# 1DD-17-mk-1_2.net
KiCad netlist of a schematic drawn in EAGLE
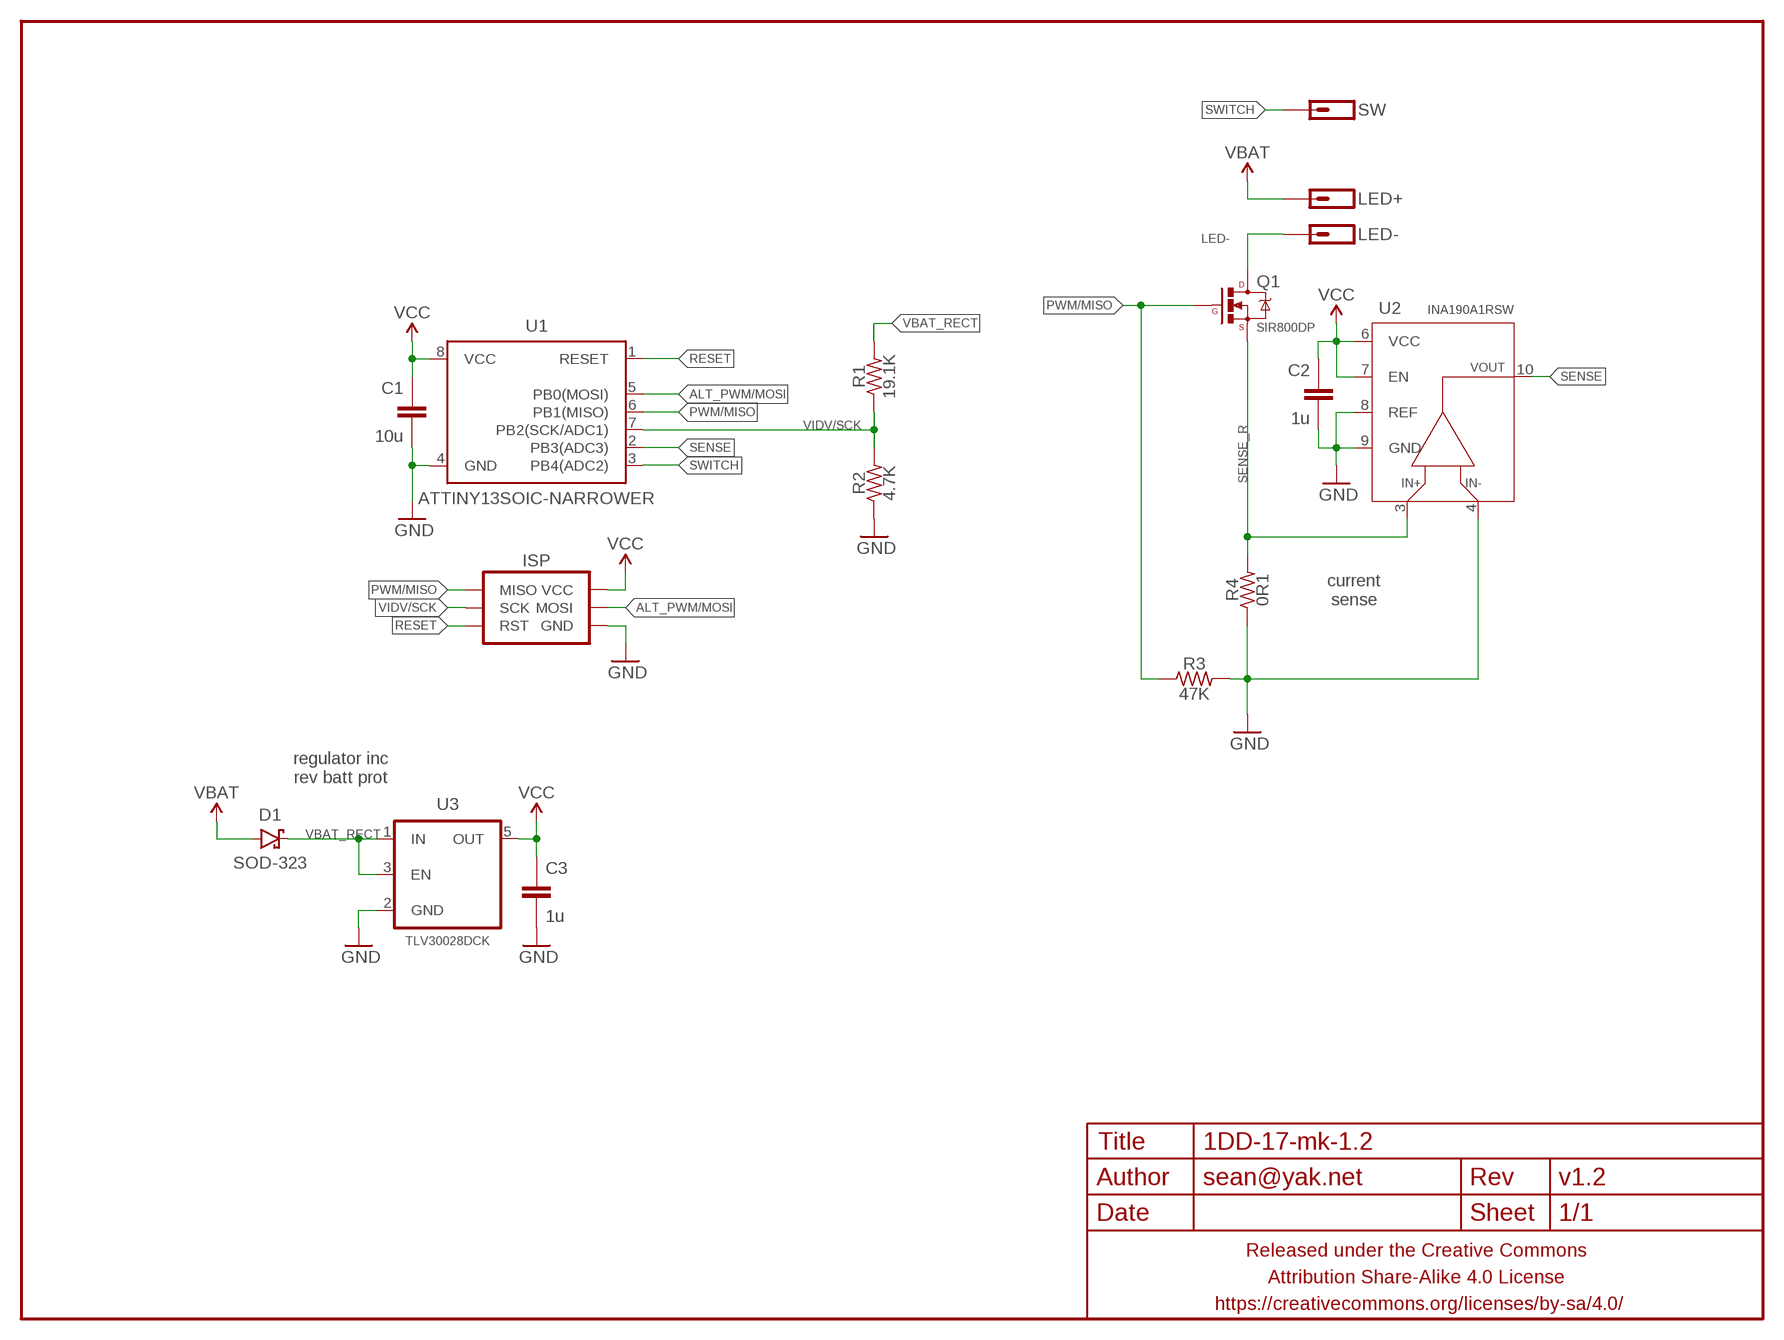
[diagram p0: schematic, sheet 1]

(export (version "E")
  (design (tool "Eeschema 10.0.6"))
  (components
    (comp (ref "C1")
      (value "10u")
      (footprint "eagle-import:C0402")
      (libsource (lib "eagle-import") (part "CAPACITOR-CERAMICC0402"))
    )
    (comp (ref "C2")
      (value "1u")
      (footprint "eagle-import:C0402")
      (libsource (lib "eagle-import") (part "CAPACITOR-CERAMICC0402"))
    )
    (comp (ref "C3")
      (value "1u")
      (footprint "eagle-import:C0402")
      (libsource (lib "eagle-import") (part "CAPACITOR-CERAMICC0402"))
    )
    (comp (ref "D1")
      (value "SOD-323")
      (footprint "eagle-import:SOD323-SCHOTTKY")
      (libsource (lib "eagle-import") (part "DIODE-SCHOTTKYSOD323"))
    )
    (comp (ref "FRAME1")
      (value "FRAME-LETTERNO_PACKAGE")
      (footprint "eagle-import:DUMMY")
      (fields
        (field (name "DESIGNER") "sean@yak.net")
        (field (name "VERSION") "v1.2")
        (field (name "DESIGNER_1") "sean@yak.net")
        (field (name "VERSION_1") "v1.2")
      )
      (libsource (lib "eagle-import") (part "FRAME-LETTERNO_PACKAGE"))
    )
    (comp (ref "ISP")
      (value "AVR_SPI_PRG_6SMD-1.27MM")
      (footprint "eagle-import:2X3-1.27MM-SMD")
      (libsource (lib "eagle-import") (part "AVR_SPI_PRG_6SMD-1.27MM"))
    )
    (comp (ref "LED+")
      (value "M01PTH-0.9MM-CIR")
      (footprint "eagle-import:1X01-0.9MM-CIR")
      (libsource (lib "eagle-import") (part "M01PTH-0.9MM-CIR"))
    )
    (comp (ref "LED-")
      (value "M01PTH-0.9MM-CIR")
      (footprint "eagle-import:1X01-0.9MM-CIR")
      (libsource (lib "eagle-import") (part "M01PTH-0.9MM-CIR"))
    )
    (comp (ref "Q1")
      (value "SIR800DP")
      (footprint "eagle-import:LFPAK56")
      (libsource (lib "eagle-import") (part "MOSFET-NCHANNELPSMN4R0-30YLD"))
    )
    (comp (ref "R1")
      (value "19.1K")
      (footprint "eagle-import:R0402")
      (libsource (lib "eagle-import") (part "RESISTORR0402"))
    )
    (comp (ref "R2")
      (value "4.7K")
      (footprint "eagle-import:R0402")
      (libsource (lib "eagle-import") (part "RESISTORR0402"))
    )
    (comp (ref "R3")
      (value "47K")
      (footprint "eagle-import:R0402")
      (libsource (lib "eagle-import") (part "RESISTORR0402"))
    )
    (comp (ref "R4")
      (value "0R1")
      (footprint "eagle-import:R0805-TIGHTER")
      (libsource (lib "eagle-import") (part "RESISTORR0805-TIGHTER"))
    )
    (comp (ref "SW")
      (value "M01SMD-1MM-DIA-NS")
      (footprint "eagle-import:1X01-SMD-1MM-DIA-NS")
      (libsource (lib "eagle-import") (part "M01SMD-1MM-DIA-NS"))
    )
    (comp (ref "U1")
      (value "ATTINY13SOIC-NARROWER")
      (footprint "eagle-import:SO08-SKINNYPADS")
      (libsource (lib "eagle-import") (part "ATTINY13SOIC-NARROWER"))
    )
    (comp (ref "U2")
      (value "INA190A1RSW")
      (footprint "eagle-import:UQFN-10")
      (libsource (lib "eagle-import") (part "INA190RSW"))
    )
    (comp (ref "U3")
      (value "TLV30028DCK")
      (footprint "eagle-import:SC70-TIGHTER")
      (libsource (lib "eagle-import") (part "V_REG_ENTLV700XXDCK-TIGHTER"))
    )
  )
  (nets
    (net (code "1") (name "/LED-") (class "Default")
      (node (ref "LED-") (pin "P$1") (pinfunction "1_P$1") (pintype "passive"))
      (node (ref "Q1") (pin "PAD") (pinfunction "D_PAD") (pintype "passive"))
    )
    (net (code "2") (name "/SENSE_R") (class "Default")
      (node (ref "Q1") (pin "1") (pinfunction "S_1") (pintype "passive"))
      (node (ref "Q1") (pin "2") (pinfunction "S_2") (pintype "passive"))
      (node (ref "Q1") (pin "3") (pinfunction "S_3") (pintype "passive"))
      (node (ref "R4") (pin "2") (pinfunction "2_2") (pintype "passive"))
      (node (ref "U2") (pin "3") (pinfunction "VIN+_3") (pintype "bidirectional"))
    )
    (net (code "3") (name "ALT_PWM{slash}MOSI") (class "Default")
      (node (ref "ISP") (pin "4") (pinfunction "MOSI_4") (pintype "passive"))
      (node (ref "U1") (pin "5") (pinfunction "PB0(MOSI)_5") (pintype "bidirectional"))
    )
    (net (code "4") (name "GND") (class "Default")
      (node (ref "C1") (pin "2") (pinfunction "2_2") (pintype "passive"))
      (node (ref "C2") (pin "2") (pinfunction "2_2") (pintype "passive"))
      (node (ref "C3") (pin "2") (pinfunction "2_2") (pintype "passive"))
      (node (ref "ISP") (pin "6") (pinfunction "GND_6") (pintype "passive"))
      (node (ref "R2") (pin "1") (pinfunction "1_1") (pintype "passive"))
      (node (ref "R3") (pin "2") (pinfunction "2_2") (pintype "passive"))
      (node (ref "R4") (pin "1") (pinfunction "1_1") (pintype "passive"))
      (node (ref "U1") (pin "4") (pinfunction "GND_4") (pintype "bidirectional"))
      (node (ref "U2") (pin "4") (pinfunction "VIN-_4") (pintype "bidirectional"))
      (node (ref "U2") (pin "8") (pinfunction "REF_8") (pintype "bidirectional"))
      (node (ref "U2") (pin "9") (pinfunction "GND_9") (pintype "bidirectional"))
      (node (ref "U3") (pin "2") (pinfunction "GND_2") (pintype "input"))
    )
    (net (code "5") (name "PWM{slash}MISO") (class "Default")
      (node (ref "ISP") (pin "1") (pinfunction "MISO_1") (pintype "passive"))
      (node (ref "Q1") (pin "4") (pinfunction "G_4") (pintype "passive"))
      (node (ref "R3") (pin "1") (pinfunction "1_1") (pintype "passive"))
      (node (ref "U1") (pin "6") (pinfunction "PB1(MISO)_6") (pintype "bidirectional"))
    )
    (net (code "6") (name "RESET") (class "Default")
      (node (ref "ISP") (pin "5") (pinfunction "RST_5") (pintype "passive"))
      (node (ref "U1") (pin "1") (pinfunction "RESET_1") (pintype "bidirectional"))
    )
    (net (code "7") (name "SENSE") (class "Default")
      (node (ref "U1") (pin "2") (pinfunction "PB3(ADC3)_2") (pintype "bidirectional"))
      (node (ref "U2") (pin "10") (pinfunction "OUT_10") (pintype "bidirectional"))
    )
    (net (code "8") (name "SWITCH") (class "Default")
      (node (ref "SW") (pin "P$1") (pinfunction "1_P$1") (pintype "passive"))
      (node (ref "U1") (pin "3") (pinfunction "PB4(ADC2)_3") (pintype "bidirectional"))
    )
    (net (code "9") (name "VBAT") (class "Default")
      (node (ref "D1") (pin "A") (pinfunction "A_A") (pintype "passive"))
      (node (ref "LED+") (pin "P$1") (pinfunction "1_P$1") (pintype "passive"))
    )
    (net (code "10") (name "VBAT_RECT") (class "Default")
      (node (ref "D1") (pin "C") (pinfunction "C_C") (pintype "passive"))
      (node (ref "R1") (pin "2") (pinfunction "2_2") (pintype "passive"))
      (node (ref "U3") (pin "1") (pinfunction "IN_1") (pintype "input"))
      (node (ref "U3") (pin "3") (pinfunction "EN_3") (pintype "input"))
    )
    (net (code "11") (name "VCC") (class "Default")
      (node (ref "C1") (pin "1") (pinfunction "1_1") (pintype "passive"))
      (node (ref "C2") (pin "1") (pinfunction "1_1") (pintype "passive"))
      (node (ref "C3") (pin "1") (pinfunction "1_1") (pintype "passive"))
      (node (ref "ISP") (pin "2") (pinfunction "VCC_2") (pintype "passive"))
      (node (ref "U1") (pin "8") (pinfunction "VCC_8") (pintype "bidirectional"))
      (node (ref "U2") (pin "6") (pinfunction "VCC_6") (pintype "bidirectional"))
      (node (ref "U2") (pin "7") (pinfunction "EN_7") (pintype "bidirectional"))
      (node (ref "U3") (pin "5") (pinfunction "OUT_5") (pintype "passive"))
    )
    (net (code "12") (name "VIDV{slash}SCK") (class "Default")
      (node (ref "ISP") (pin "3") (pinfunction "SCK_3") (pintype "passive"))
      (node (ref "R1") (pin "1") (pinfunction "1_1") (pintype "passive"))
      (node (ref "R2") (pin "2") (pinfunction "2_2") (pintype "passive"))
      (node (ref "U1") (pin "7") (pinfunction "PB2(SCK/ADC1)_7") (pintype "bidirectional"))
    )
  )
)
